# MinieasySens-RS485_V13-Build023.net
KiCad netlist of a schematic drawn in EAGLE
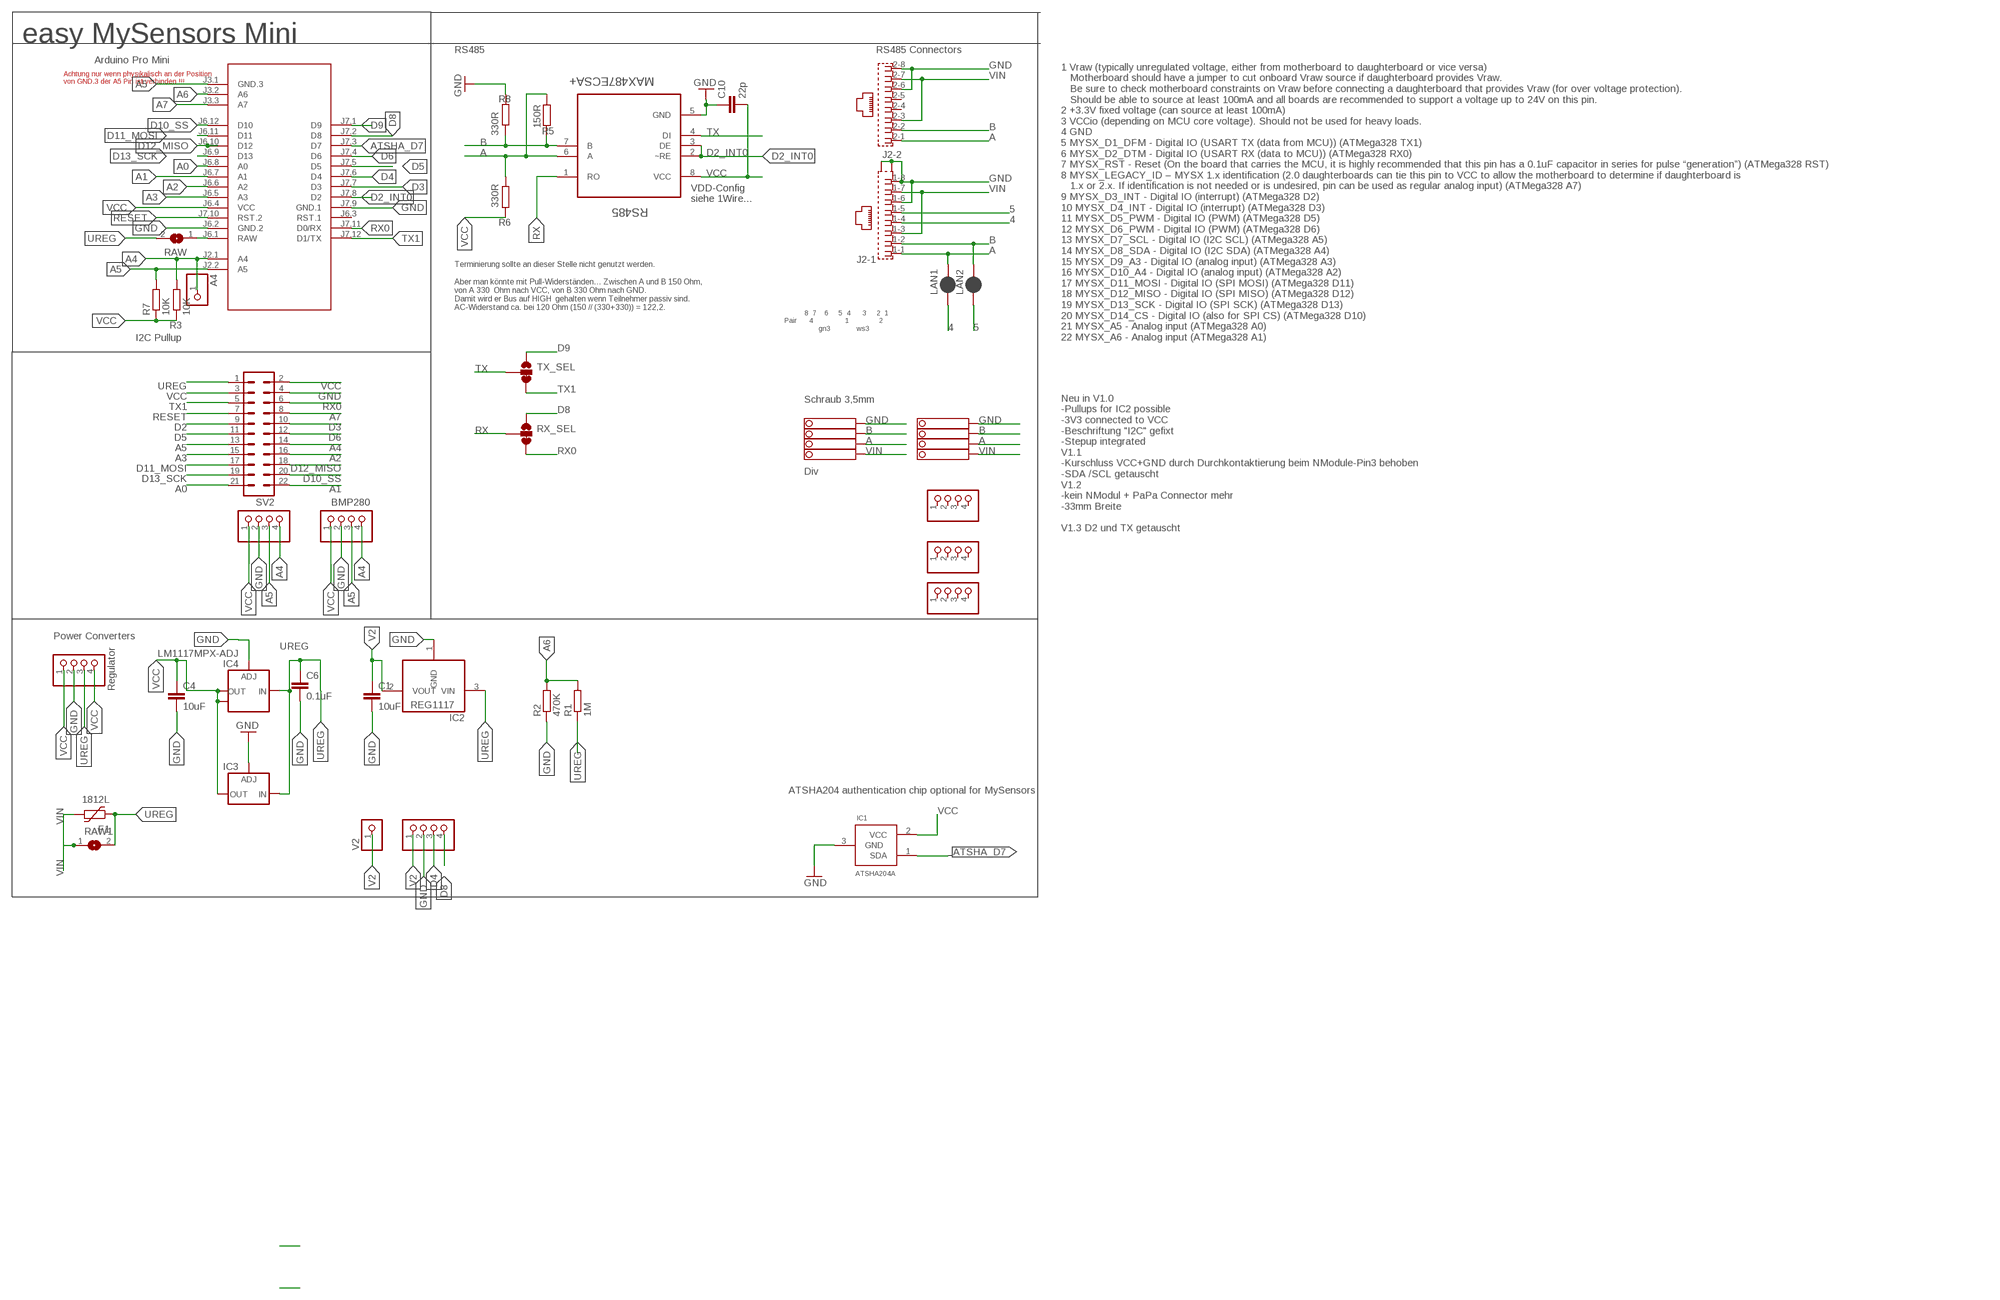
[diagram p0: schematic, sheet 1]

(export (version "E")
  (design (tool "Eeschema 10.0.6"))
  (components
    (comp (ref "A4")
      (value "PINHD-1X1")
      (footprint "eagle-import:1X01")
      (libsource (lib "eagle-import") (part "PINHD-1X1"))
    )
    (comp (ref "BH1750")
      (value "PINHD-1X04_2.54-S")
      (footprint "eagle-import:1X04-S")
      (libsource (lib "eagle-import") (part "PINHD-1X04_2.54-S"))
    )
    (comp (ref "C1")
      (value "10uF")
      (footprint "eagle-import:C1210")
      (libsource (lib "eagle-import") (part "C-EUC1210"))
    )
    (comp (ref "C4")
      (value "10uF")
      (footprint "eagle-import:C1210")
      (libsource (lib "eagle-import") (part "C-EUC1210"))
    )
    (comp (ref "C6")
      (value "0.1uF")
      (footprint "eagle-import:C1206")
      (libsource (lib "eagle-import") (part "C-EUC1206"))
    )
    (comp (ref "C10")
      (value "22p")
      (footprint "eagle-import:C0805")
      (libsource (lib "eagle-import") (part "C-EUC0805"))
    )
    (comp (ref "F1")
      (value "1812L")
      (footprint "eagle-import:1812L")
      (libsource (lib "eagle-import") (part "1812L"))
    )
    (comp (ref "I2C-1")
      (value "PINHD-1X04_2.54-S")
      (footprint "eagle-import:1X04-S")
      (libsource (lib "eagle-import") (part "PINHD-1X04_2.54-S"))
    )
    (comp (ref "IC1")
      (value "ATSHA204A")
      (footprint "eagle-import:SOT23")
      (libsource (lib "eagle-import") (part "ATSHA204A"))
    )
    (comp (ref "IC2")
      (value "REG1117")
      (footprint "eagle-import:SOT223")
      (libsource (lib "eagle-import") (part "REG1117"))
    )
    (comp (ref "IC3")
      (value "LD117ADT50TR")
      (footprint "eagle-import:DPACK")
      (libsource (lib "eagle-import") (part "LD117A?DT50TR"))
    )
    (comp (ref "IC4")
      (value "LM1117MPX-ADJ")
      (footprint "eagle-import:SOT223")
      (libsource (lib "eagle-import") (part "LM1117MPX-ADJ"))
    )
    (comp (ref "J2")
      (value "RJ45_2X_NARROW_SHILDPINS_NOCASE")
      (footprint "eagle-import:RJ45_2X_NARROW_SHILDPINS_NOCASE")
      (libsource (lib "eagle-import") (part "RJ45_2X_NARROW_SHILDPINS_NOCASE"))
    )
    (comp (ref "JP1")
      (value "PINHD-1X04_2.54-S")
      (footprint "eagle-import:1X04-S")
      (libsource (lib "eagle-import") (part "PINHD-1X04_2.54-S"))
    )
    (comp (ref "JP2")
      (value "PINHD-1X04_2.54-S")
      (footprint "eagle-import:1X04-S")
      (libsource (lib "eagle-import") (part "PINHD-1X04_2.54-S"))
    )
    (comp (ref "JP4")
      (value "PINHD-1X04_2.54-S")
      (footprint "eagle-import:1X04-S")
      (libsource (lib "eagle-import") (part "PINHD-1X04_2.54-S"))
    )
    (comp (ref "LAN1")
      (value "JUMPER-SMT_2_NC_PASTE_SILK")
      (footprint "eagle-import:SMT-JUMPER_2_NC_PASTE_SILK")
      (libsource (lib "eagle-import") (part "JUMPER-SMT_2_NC_PASTE_SILK"))
    )
    (comp (ref "LAN2")
      (value "JUMPER-SMT_2_NC_PASTE_SILK")
      (footprint "eagle-import:SMT-JUMPER_2_NC_PASTE_SILK")
      (libsource (lib "eagle-import") (part "JUMPER-SMT_2_NC_PASTE_SILK"))
    )
    (comp (ref "M1")
      (value "ARDUINO-PRO-MINI-3.3V#NP")
      (footprint "eagle-import:ARDUINO-PRO-MINI#NP")
      (libsource (lib "eagle-import") (part "ARDUINO-PRO-MINI-#NP3.3V"))
    )
    (comp (ref "R1")
      (value "1M")
      (footprint "eagle-import:R0805")
      (libsource (lib "eagle-import") (part "R-EU_R0805"))
    )
    (comp (ref "R2")
      (value "470K")
      (footprint "eagle-import:R0805")
      (libsource (lib "eagle-import") (part "R-EU_R0805"))
    )
    (comp (ref "R3")
      (value "10K")
      (footprint "eagle-import:R0805")
      (libsource (lib "eagle-import") (part "R-EU_R0805"))
    )
    (comp (ref "R5")
      (value "150R")
      (footprint "eagle-import:R0805")
      (libsource (lib "eagle-import") (part "R-EU_R0805"))
    )
    (comp (ref "R6")
      (value "330R")
      (footprint "eagle-import:R0805")
      (libsource (lib "eagle-import") (part "R-EU_R0805"))
    )
    (comp (ref "R7")
      (value "10K")
      (footprint "eagle-import:R0805")
      (libsource (lib "eagle-import") (part "R-EU_R0805"))
    )
    (comp (ref "R8")
      (value "330R")
      (footprint "eagle-import:R0805")
      (libsource (lib "eagle-import") (part "R-EU_R0805"))
    )
    (comp (ref "RAW") (value "SJ") (footprint "eagle-import:SJ") (libsource (lib "eagle-import") (part "SJ")))
    (comp (ref "RAW1")
      (value "SJ")
      (footprint "eagle-import:SJ")
      (libsource (lib "eagle-import") (part "SJ"))
    )
    (comp (ref "RS485")
      (value "MAX487ECSA+")
      (footprint "eagle-import:SOIC127P600X175-8N")
      (libsource (lib "eagle-import") (part "MAX487ECSA+"))
    )
    (comp (ref "RX_SEL")
      (value "JUMPER-SMT_3_1-NC_TRACE_SILK")
      (footprint "eagle-import:SMT-JUMPER_3_1-NC_TRACE_SILK")
      (libsource (lib "eagle-import") (part "JUMPER-SMT_3_1-NC_TRACE_SILK"))
    )
    (comp (ref "STEPDWN")
      (value "PINHD-1X04_2.54-S")
      (footprint "eagle-import:1X04-S")
      (libsource (lib "eagle-import") (part "PINHD-1X04_2.54-S"))
    )
    (comp (ref "SV2")
      (value "MA11-2")
      (footprint "eagle-import:MA11-2")
      (libsource (lib "eagle-import") (part "MA11-2"))
    )
    (comp (ref "TX_SEL")
      (value "JUMPER-SMT_3_1-NC_TRACE_SILK")
      (footprint "eagle-import:SMT-JUMPER_3_1-NC_TRACE_SILK")
      (libsource (lib "eagle-import") (part "JUMPER-SMT_3_1-NC_TRACE_SILK"))
    )
    (comp (ref "V2")
      (value "PINHD-1X1")
      (footprint "eagle-import:1X01")
      (libsource (lib "eagle-import") (part "PINHD-1X1"))
    )
    (comp (ref "V2-")
      (value "PINHD-1X04_2.54-S")
      (footprint "eagle-import:1X04-S")
      (libsource (lib "eagle-import") (part "PINHD-1X04_2.54-S"))
    )
    (comp (ref "X1")
      (value "1751264")
      (footprint "eagle-import:1751264")
      (libsource (lib "eagle-import") (part "1751264"))
    )
    (comp (ref "X4")
      (value "1751264")
      (footprint "eagle-import:1751264")
      (libsource (lib "eagle-import") (part "1751264"))
    )
  )
  (nets
    (net (code "1") (name "/4") (class "Default")
      (node (ref "J2") (pin "1-4") (pinfunction "4_1-4") (pintype "passive"))
      (node (ref "LAN1") (pin "1") (pinfunction "1_1") (pintype "passive"))
    )
    (net (code "2") (name "/5") (class "Default")
      (node (ref "J2") (pin "1-5") (pinfunction "5_1-5") (pintype "passive"))
      (node (ref "LAN2") (pin "1") (pinfunction "1_1") (pintype "passive"))
    )
    (net (code "3") (name "/A") (class "Default")
      (node (ref "J2") (pin "1-1") (pinfunction "1_1-1") (pintype "passive"))
      (node (ref "J2") (pin "2-1") (pinfunction "1_2-1") (pintype "passive"))
      (node (ref "LAN1") (pin "2") (pinfunction "2_2") (pintype "passive"))
      (node (ref "R5") (pin "1") (pinfunction "1_1") (pintype "passive"))
      (node (ref "R6") (pin "2") (pinfunction "2_2") (pintype "passive"))
      (node (ref "RS485") (pin "6") (pinfunction "A_6") (pintype "bidirectional"))
      (node (ref "X1") (pin "2") (pinfunction "K_2") (pintype "passive"))
      (node (ref "X4") (pin "2") (pinfunction "K_2") (pintype "passive"))
    )
    (net (code "4") (name "/B") (class "Default")
      (node (ref "J2") (pin "1-2") (pinfunction "2_1-2") (pintype "passive"))
      (node (ref "J2") (pin "2-2") (pinfunction "2_2-2") (pintype "passive"))
      (node (ref "LAN2") (pin "2") (pinfunction "2_2") (pintype "passive"))
      (node (ref "R5") (pin "2") (pinfunction "2_2") (pintype "passive"))
      (node (ref "R8") (pin "1") (pinfunction "1_1") (pintype "passive"))
      (node (ref "RS485") (pin "7") (pinfunction "B_7") (pintype "bidirectional"))
      (node (ref "X1") (pin "3") (pinfunction "K_3") (pintype "passive"))
      (node (ref "X4") (pin "3") (pinfunction "K_3") (pintype "passive"))
    )
    (net (code "5") (name "/D2") (class "Default")
      (node (ref "SV2") (pin "9") (pinfunction "9_9") (pintype "passive"))
    )
    (net (code "6") (name "/TX") (class "Default")
      (node (ref "RS485") (pin "4") (pinfunction "DI_4") (pintype "input"))
      (node (ref "TX_SEL") (pin "2") (pinfunction "2_2") (pintype "passive"))
    )
    (net (code "7") (name "/VIN") (class "Default")
      (node (ref "F1") (pin "P$2") (pinfunction "2_P$2") (pintype "passive"))
      (node (ref "J2") (pin "1-3") (pinfunction "3_1-3") (pintype "passive"))
      (node (ref "J2") (pin "1-7") (pinfunction "7_1-7") (pintype "passive"))
      (node (ref "J2") (pin "2-3") (pinfunction "3_2-3") (pintype "passive"))
      (node (ref "J2") (pin "2-7") (pinfunction "7_2-7") (pintype "passive"))
      (node (ref "RAW1") (pin "1") (pinfunction "1_1") (pintype "passive"))
      (node (ref "X1") (pin "1") (pinfunction "K_1") (pintype "passive"))
      (node (ref "X4") (pin "1") (pinfunction "K_1") (pintype "passive"))
    )
    (net (code "8") (name "A0") (class "Default")
      (node (ref "M1") (pin "J6.8") (pinfunction "A0_J6.8") (pintype "bidirectional"))
      (node (ref "SV2") (pin "21") (pinfunction "21_21") (pintype "passive"))
    )
    (net (code "9") (name "A1") (class "Default")
      (node (ref "M1") (pin "J6.7") (pinfunction "A1_J6.7") (pintype "bidirectional"))
      (node (ref "SV2") (pin "22") (pinfunction "22_22") (pintype "passive"))
    )
    (net (code "10") (name "A2") (class "Default")
      (node (ref "M1") (pin "J6.6") (pinfunction "A2_J6.6") (pintype "bidirectional"))
      (node (ref "SV2") (pin "16") (pinfunction "16_16") (pintype "passive"))
    )
    (net (code "11") (name "A3") (class "Default")
      (node (ref "M1") (pin "J6.5") (pinfunction "A3_J6.5") (pintype "bidirectional"))
      (node (ref "SV2") (pin "15") (pinfunction "15_15") (pintype "passive"))
    )
    (net (code "12") (name "A4") (class "Default")
      (node (ref "A4") (pin "1") (pinfunction "1_1") (pintype "passive"))
      (node (ref "BH1750") (pin "4") (pinfunction "4_4") (pintype "passive"))
      (node (ref "I2C-1") (pin "4") (pinfunction "4_4") (pintype "passive"))
      (node (ref "M1") (pin "J2.1") (pinfunction "A4_J2.1") (pintype "bidirectional"))
      (node (ref "R3") (pin "2") (pinfunction "2_2") (pintype "passive"))
      (node (ref "SV2") (pin "14") (pinfunction "14_14") (pintype "passive"))
    )
    (net (code "13") (name "A5") (class "Default")
      (node (ref "BH1750") (pin "3") (pinfunction "3_3") (pintype "passive"))
      (node (ref "I2C-1") (pin "3") (pinfunction "3_3") (pintype "passive"))
      (node (ref "M1") (pin "J2.2") (pinfunction "A5_J2.2") (pintype "bidirectional"))
      (node (ref "M1") (pin "J3.1") (pinfunction "GND.3_J3.1") (pintype "bidirectional"))
      (node (ref "R7") (pin "2") (pinfunction "2_2") (pintype "passive"))
      (node (ref "SV2") (pin "13") (pinfunction "13_13") (pintype "passive"))
    )
    (net (code "14") (name "A6") (class "Default")
      (node (ref "M1") (pin "J3.2") (pinfunction "A6_J3.2") (pintype "bidirectional"))
      (node (ref "R1") (pin "2") (pinfunction "2_2") (pintype "passive"))
      (node (ref "R2") (pin "2") (pinfunction "2_2") (pintype "passive"))
    )
    (net (code "15") (name "A7") (class "Default")
      (node (ref "M1") (pin "J3.3") (pinfunction "A7_J3.3") (pintype "bidirectional"))
      (node (ref "SV2") (pin "8") (pinfunction "8_8") (pintype "passive"))
    )
    (net (code "16") (name "ATSHA_D7") (class "Default")
      (node (ref "IC1") (pin "1") (pinfunction "SDA_1") (pintype "bidirectional"))
      (node (ref "M1") (pin "J7.3") (pinfunction "D7_J7.3") (pintype "bidirectional"))
    )
    (net (code "17") (name "D2_INT0") (class "Default")
      (node (ref "M1") (pin "J7.8") (pinfunction "D2_J7.8") (pintype "bidirectional"))
      (node (ref "RS485") (pin "2") (pinfunction "~{RE}_2") (pintype "input"))
      (node (ref "RS485") (pin "3") (pinfunction "DE_3") (pintype "input"))
    )
    (net (code "18") (name "D3") (class "Default")
      (node (ref "M1") (pin "J7.7") (pinfunction "D3_J7.7") (pintype "bidirectional"))
      (node (ref "SV2") (pin "10") (pinfunction "10_10") (pintype "passive"))
    )
    (net (code "19") (name "D4") (class "Default")
      (node (ref "M1") (pin "J7.6") (pinfunction "D4_J7.6") (pintype "bidirectional"))
      (node (ref "V2-") (pin "3") (pinfunction "3_3") (pintype "passive"))
    )
    (net (code "20") (name "D5") (class "Default")
      (node (ref "M1") (pin "J7.5") (pinfunction "D5_J7.5") (pintype "bidirectional"))
      (node (ref "SV2") (pin "11") (pinfunction "11_11") (pintype "passive"))
    )
    (net (code "21") (name "D6") (class "Default")
      (node (ref "M1") (pin "J7.4") (pinfunction "D6_J7.4") (pintype "bidirectional"))
      (node (ref "SV2") (pin "12") (pinfunction "12_12") (pintype "passive"))
    )
    (net (code "22") (name "D8") (class "Default")
      (node (ref "M1") (pin "J7.2") (pinfunction "D8_J7.2") (pintype "bidirectional"))
      (node (ref "RX_SEL") (pin "1") (pinfunction "1_1") (pintype "passive"))
      (node (ref "V2-") (pin "4") (pinfunction "4_4") (pintype "passive"))
    )
    (net (code "23") (name "D9") (class "Default")
      (node (ref "M1") (pin "J7.1") (pinfunction "D9_J7.1") (pintype "bidirectional"))
      (node (ref "TX_SEL") (pin "1") (pinfunction "1_1") (pintype "passive"))
    )
    (net (code "24") (name "D10_SS") (class "Default")
      (node (ref "M1") (pin "J6.12") (pinfunction "D10_J6.12") (pintype "bidirectional"))
      (node (ref "SV2") (pin "20") (pinfunction "20_20") (pintype "passive"))
    )
    (net (code "25") (name "D11_MOSI") (class "Default")
      (node (ref "M1") (pin "J6.11") (pinfunction "D11_J6.11") (pintype "bidirectional"))
      (node (ref "SV2") (pin "17") (pinfunction "17_17") (pintype "passive"))
    )
    (net (code "26") (name "D12_MISO") (class "Default")
      (node (ref "M1") (pin "J6.10") (pinfunction "D12_J6.10") (pintype "bidirectional"))
      (node (ref "SV2") (pin "18") (pinfunction "18_18") (pintype "passive"))
    )
    (net (code "27") (name "D13_SCK") (class "Default")
      (node (ref "M1") (pin "J6.9") (pinfunction "D13_J6.9") (pintype "bidirectional"))
      (node (ref "SV2") (pin "19") (pinfunction "19_19") (pintype "passive"))
    )
    (net (code "28") (name "GND") (class "Default")
      (node (ref "BH1750") (pin "2") (pinfunction "2_2") (pintype "passive"))
      (node (ref "C1") (pin "2") (pinfunction "2_2") (pintype "passive"))
      (node (ref "C10") (pin "1") (pinfunction "1_1") (pintype "passive"))
      (node (ref "C4") (pin "2") (pinfunction "2_2") (pintype "passive"))
      (node (ref "C6") (pin "2") (pinfunction "2_2") (pintype "passive"))
      (node (ref "I2C-1") (pin "2") (pinfunction "2_2") (pintype "passive"))
      (node (ref "IC1") (pin "3") (pinfunction "GND_3") (pintype "bidirectional"))
      (node (ref "IC2") (pin "1") (pinfunction "GND_1") (pintype "power_in"))
      (node (ref "IC3") (pin "1") (pinfunction "ADJ_1") (pintype "input"))
      (node (ref "IC4") (pin "1") (pinfunction "ADJ_1") (pintype "input"))
      (node (ref "J2") (pin "1-6") (pinfunction "6_1-6") (pintype "passive"))
      (node (ref "J2") (pin "1-8") (pinfunction "8_1-8") (pintype "passive"))
      (node (ref "J2") (pin "2-6") (pinfunction "6_2-6") (pintype "passive"))
      (node (ref "J2") (pin "2-8") (pinfunction "8_2-8") (pintype "passive"))
      (node (ref "J2") (pin "G1") (pinfunction "S1_G1") (pintype "passive"))
      (node (ref "J2") (pin "G3") (pinfunction "S2_G3") (pintype "passive"))
      (node (ref "M1") (pin "J6.2") (pinfunction "GND.2_J6.2") (pintype "power_in"))
      (node (ref "M1") (pin "J7.9") (pinfunction "GND.1_J7.9") (pintype "power_in"))
      (node (ref "R2") (pin "1") (pinfunction "1_1") (pintype "passive"))
      (node (ref "R8") (pin "2") (pinfunction "2_2") (pintype "passive"))
      (node (ref "RS485") (pin "5") (pinfunction "GND_5") (pintype "passive"))
      (node (ref "STEPDWN") (pin "2") (pinfunction "2_2") (pintype "passive"))
      (node (ref "SV2") (pin "4") (pinfunction "4_4") (pintype "passive"))
      (node (ref "V2-") (pin "2") (pinfunction "2_2") (pintype "passive"))
      (node (ref "X1") (pin "4") (pinfunction "K_4") (pintype "passive"))
      (node (ref "X4") (pin "4") (pinfunction "K_4") (pintype "passive"))
    )
    (net (code "29") (name "Net-(M1-RAW)") (class "Default")
      (node (ref "M1") (pin "J6.1") (pinfunction "RAW_J6.1") (pintype "power_in"))
      (node (ref "RAW") (pin "1") (pinfunction "1_1") (pintype "passive"))
    )
    (net (code "30") (name "RESET") (class "Default")
      (node (ref "M1") (pin "J7.10") (pinfunction "RST.2_J7.10") (pintype "bidirectional"))
      (node (ref "SV2") (pin "7") (pinfunction "7_7") (pintype "passive"))
    )
    (net (code "31") (name "RX") (class "Default")
      (node (ref "RS485") (pin "1") (pinfunction "RO_1") (pintype "output"))
      (node (ref "RX_SEL") (pin "2") (pinfunction "2_2") (pintype "passive"))
    )
    (net (code "32") (name "RX0") (class "Default")
      (node (ref "M1") (pin "J7.11") (pinfunction "D0/RX_J7.11") (pintype "bidirectional"))
      (node (ref "RX_SEL") (pin "3") (pinfunction "3_3") (pintype "passive"))
      (node (ref "SV2") (pin "6") (pinfunction "6_6") (pintype "passive"))
    )
    (net (code "33") (name "TX1") (class "Default")
      (node (ref "M1") (pin "J7.12") (pinfunction "D1/TX_J7.12") (pintype "bidirectional"))
      (node (ref "SV2") (pin "5") (pinfunction "5_5") (pintype "passive"))
      (node (ref "TX_SEL") (pin "3") (pinfunction "3_3") (pintype "passive"))
    )
    (net (code "34") (name "UREG") (class "Default")
      (node (ref "C6") (pin "1") (pinfunction "1_1") (pintype "passive"))
      (node (ref "F1") (pin "P$1") (pinfunction "1_P$1") (pintype "passive"))
      (node (ref "IC2") (pin "3") (pinfunction "VIN_3") (pintype "input"))
      (node (ref "IC3") (pin "3") (pinfunction "IN_3") (pintype "input"))
      (node (ref "IC4") (pin "3") (pinfunction "IN_3") (pintype "input"))
      (node (ref "R1") (pin "1") (pinfunction "1_1") (pintype "passive"))
      (node (ref "RAW") (pin "2") (pinfunction "2_2") (pintype "passive"))
      (node (ref "RAW1") (pin "2") (pinfunction "2_2") (pintype "passive"))
      (node (ref "STEPDWN") (pin "3") (pinfunction "3_3") (pintype "passive"))
      (node (ref "SV2") (pin "1") (pinfunction "1_1") (pintype "passive"))
    )
    (net (code "35") (name "V2") (class "Default")
      (node (ref "C1") (pin "1") (pinfunction "1_1") (pintype "passive"))
      (node (ref "IC2") (pin "2") (pinfunction "VOUT_2") (pintype "output"))
      (node (ref "V2") (pin "1") (pinfunction "1_1") (pintype "passive"))
      (node (ref "V2-") (pin "1") (pinfunction "1_1") (pintype "passive"))
    )
    (net (code "36") (name "VCC") (class "Default")
      (node (ref "BH1750") (pin "1") (pinfunction "1_1") (pintype "passive"))
      (node (ref "C10") (pin "2") (pinfunction "2_2") (pintype "passive"))
      (node (ref "C4") (pin "1") (pinfunction "1_1") (pintype "passive"))
      (node (ref "I2C-1") (pin "1") (pinfunction "1_1") (pintype "passive"))
      (node (ref "IC1") (pin "2") (pinfunction "VCC_2") (pintype "bidirectional"))
      (node (ref "IC3") (pin "4") (pinfunction "OUT_4") (pintype "passive"))
      (node (ref "IC4") (pin "2") (pinfunction "OUT_2") (pintype "passive"))
      (node (ref "IC4") (pin "TAB") (pinfunction "OUT1_TAB") (pintype "passive"))
      (node (ref "M1") (pin "J6.4") (pinfunction "VCC_J6.4") (pintype "power_in"))
      (node (ref "R3") (pin "1") (pinfunction "1_1") (pintype "passive"))
      (node (ref "R6") (pin "1") (pinfunction "1_1") (pintype "passive"))
      (node (ref "R7") (pin "1") (pinfunction "1_1") (pintype "passive"))
      (node (ref "RS485") (pin "8") (pinfunction "VCC_8") (pintype "power_in"))
      (node (ref "STEPDWN") (pin "1") (pinfunction "1_1") (pintype "passive"))
      (node (ref "STEPDWN") (pin "4") (pinfunction "4_4") (pintype "passive"))
      (node (ref "SV2") (pin "2") (pinfunction "2_2") (pintype "passive"))
      (node (ref "SV2") (pin "3") (pinfunction "3_3") (pintype "passive"))
    )
    (net (code "37") (name "unconnected-(J2B-4-Pad2-4)") (class "Default")
      (node (ref "J2") (pin "2-4") (pinfunction "4_2-4") (pintype "passive"))
    )
    (net (code "38") (name "unconnected-(J2B-5-Pad2-5)") (class "Default")
      (node (ref "J2") (pin "2-5") (pinfunction "5_2-5") (pintype "passive"))
    )
    (net (code "39") (name "unconnected-(JP1-Pad1)") (class "Default")
      (node (ref "JP1") (pin "1") (pinfunction "1_1") (pintype "passive"))
    )
    (net (code "40") (name "unconnected-(JP1-Pad2)") (class "Default")
      (node (ref "JP1") (pin "2") (pinfunction "2_2") (pintype "passive"))
    )
    (net (code "41") (name "unconnected-(JP1-Pad3)") (class "Default")
      (node (ref "JP1") (pin "3") (pinfunction "3_3") (pintype "passive"))
    )
    (net (code "42") (name "unconnected-(JP1-Pad4)") (class "Default")
      (node (ref "JP1") (pin "4") (pinfunction "4_4") (pintype "passive"))
    )
    (net (code "43") (name "unconnected-(JP2-Pad1)") (class "Default")
      (node (ref "JP2") (pin "1") (pinfunction "1_1") (pintype "passive"))
    )
    (net (code "44") (name "unconnected-(JP2-Pad2)") (class "Default")
      (node (ref "JP2") (pin "2") (pinfunction "2_2") (pintype "passive"))
    )
    (net (code "45") (name "unconnected-(JP2-Pad3)") (class "Default")
      (node (ref "JP2") (pin "3") (pinfunction "3_3") (pintype "passive"))
    )
    (net (code "46") (name "unconnected-(JP2-Pad4)") (class "Default")
      (node (ref "JP2") (pin "4") (pinfunction "4_4") (pintype "passive"))
    )
    (net (code "47") (name "unconnected-(JP4-Pad1)") (class "Default")
      (node (ref "JP4") (pin "1") (pinfunction "1_1") (pintype "passive"))
    )
    (net (code "48") (name "unconnected-(JP4-Pad2)") (class "Default")
      (node (ref "JP4") (pin "2") (pinfunction "2_2") (pintype "passive"))
    )
    (net (code "49") (name "unconnected-(JP4-Pad3)") (class "Default")
      (node (ref "JP4") (pin "3") (pinfunction "3_3") (pintype "passive"))
    )
    (net (code "50") (name "unconnected-(JP4-Pad4)") (class "Default")
      (node (ref "JP4") (pin "4") (pinfunction "4_4") (pintype "passive"))
    )
    (net (code "51") (name "unconnected-(M1-RST.1-PadJ6.3)") (class "Default")
      (node (ref "M1") (pin "J6.3") (pinfunction "RST.1_J6.3") (pintype "bidirectional"))
    )
  )
)
